# Power.net
KiCad netlist of a schematic drawn in Altium Designer
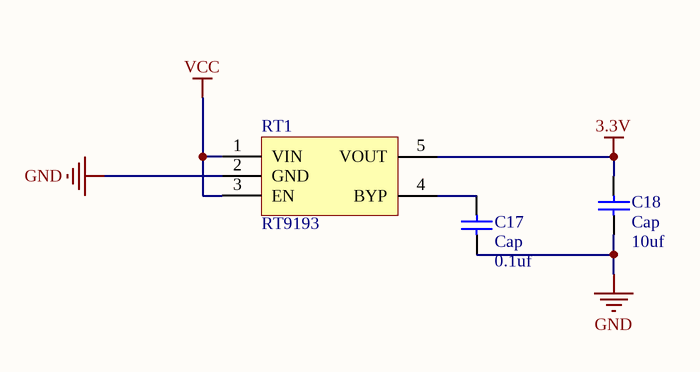
[diagram p0: Power.SchDoc]

(export (version "E")
  (design (tool "Eeschema 10.0.6"))
  (components
    (comp (ref "C17")
      (value "Cap")
      (footprint "CAP_0402")
      (description "Capacitor")
      (fields (field (name "ALTIUM_VALUE") "0.1uf") (field (name "PUBLISHER") "Altium Limited"))
      (libsource (lib "Miscellaneous Devices") (part "Cap"))
    )
    (comp (ref "C18")
      (value "Cap")
      (footprint "GeekIMU:CAP_0603")
      (description "Capacitor")
      (fields (field (name "ALTIUM_VALUE") "10uf") (field (name "PUBLISHER") "Altium Limited"))
      (libsource (lib "Miscellaneous Devices") (part "Cap"))
    )
    (comp (ref "RT1")
      (value "RT9193")
      (footprint "SOT23-5L")
      (description "Power")
      (libsource (lib "SmartIMU") (part "RT9193"))
    )
  )
  (nets
    (net (code "1") (name "3.3V") (class "Default")
      (node (ref "C18") (pin "2") (pinfunction "2_2") (pintype "passive"))
      (node (ref "RT1") (pin "5") (pinfunction "VOUT_5") (pintype "passive"))
    )
    (net (code "2") (name "GND") (class "Default")
      (node (ref "C17") (pin "1") (pinfunction "1_1") (pintype "passive"))
      (node (ref "C18") (pin "1") (pinfunction "1_1") (pintype "passive"))
      (node (ref "RT1") (pin "2") (pinfunction "GND_2") (pintype "passive"))
    )
    (net (code "3") (name "Net-(RT1-BYP)") (class "Default")
      (node (ref "C17") (pin "2") (pinfunction "2_2") (pintype "passive"))
      (node (ref "RT1") (pin "4") (pinfunction "BYP_4") (pintype "passive"))
    )
    (net (code "4") (name "VCC") (class "Default")
      (node (ref "RT1") (pin "1") (pinfunction "VIN_1") (pintype "passive"))
      (node (ref "RT1") (pin "3") (pinfunction "EN_3") (pintype "power_in"))
    )
  )
)
